# led.net
KiCad netlist of a schematic drawn in Altium Designer
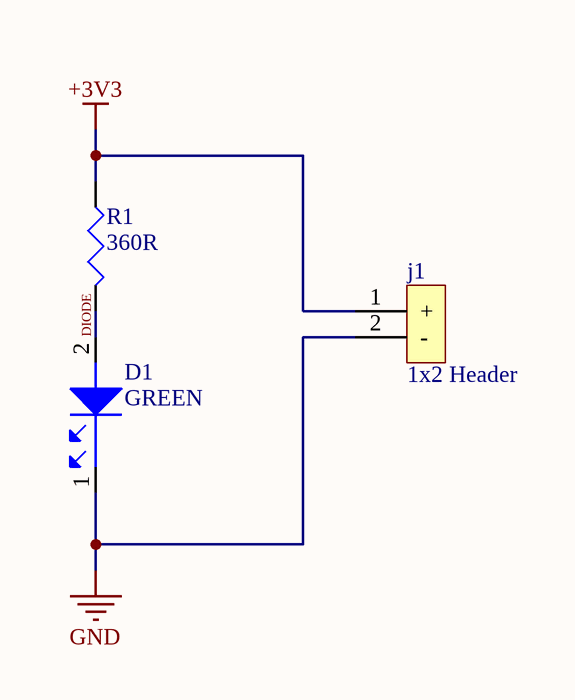
[diagram p0: led.SchDoc]

(export (version "E")
  (design (tool "Eeschema 10.0.6"))
  (components
    (comp (ref "D1")
      (value "GREEN")
      (footprint "GREEN")
      (description "LED GREEN ESS II SMD")
      (libsource (lib "led") (part "LNJ337W83RA"))
    )
    (comp (ref "j1")
      (value "1x2 Header")
      (footprint "HDR1x2")
      (description "CONN HEADER VERT 2POS 2.54MM")
      (libsource (lib "led") (part "22-29-2021"))
    )
    (comp (ref "R1")
      (value "360R")
      (footprint "R0805")
      (description "RES SMD 360K OHM 1% 1/2W 0805")
      (fields (field (name "TOLERANCE") "1%"))
      (libsource (lib "led") (part "CRCW0805360KFKEAHP"))
    )
  )
  (nets
    (net (code "1") (name "+3V3") (class "Default")
      (node (ref "R1") (pin "1") (pinfunction "9_1") (pintype "passive"))
      (node (ref "j1") (pin "1") (pinfunction "+_1") (pintype "passive"))
    )
    (net (code "2") (name "/DIODE") (class "Default")
      (node (ref "D1") (pin "2") (pinfunction "2_2") (pintype "passive"))
      (node (ref "R1") (pin "2") (pinfunction "10_2") (pintype "passive"))
    )
    (net (code "3") (name "GND") (class "Default")
      (node (ref "D1") (pin "1") (pinfunction "1_1") (pintype "passive"))
      (node (ref "j1") (pin "2") (pinfunction "-_2") (pintype "passive"))
    )
  )
)
